# Item.net
KiCad netlist of a schematic drawn in Altium Designer
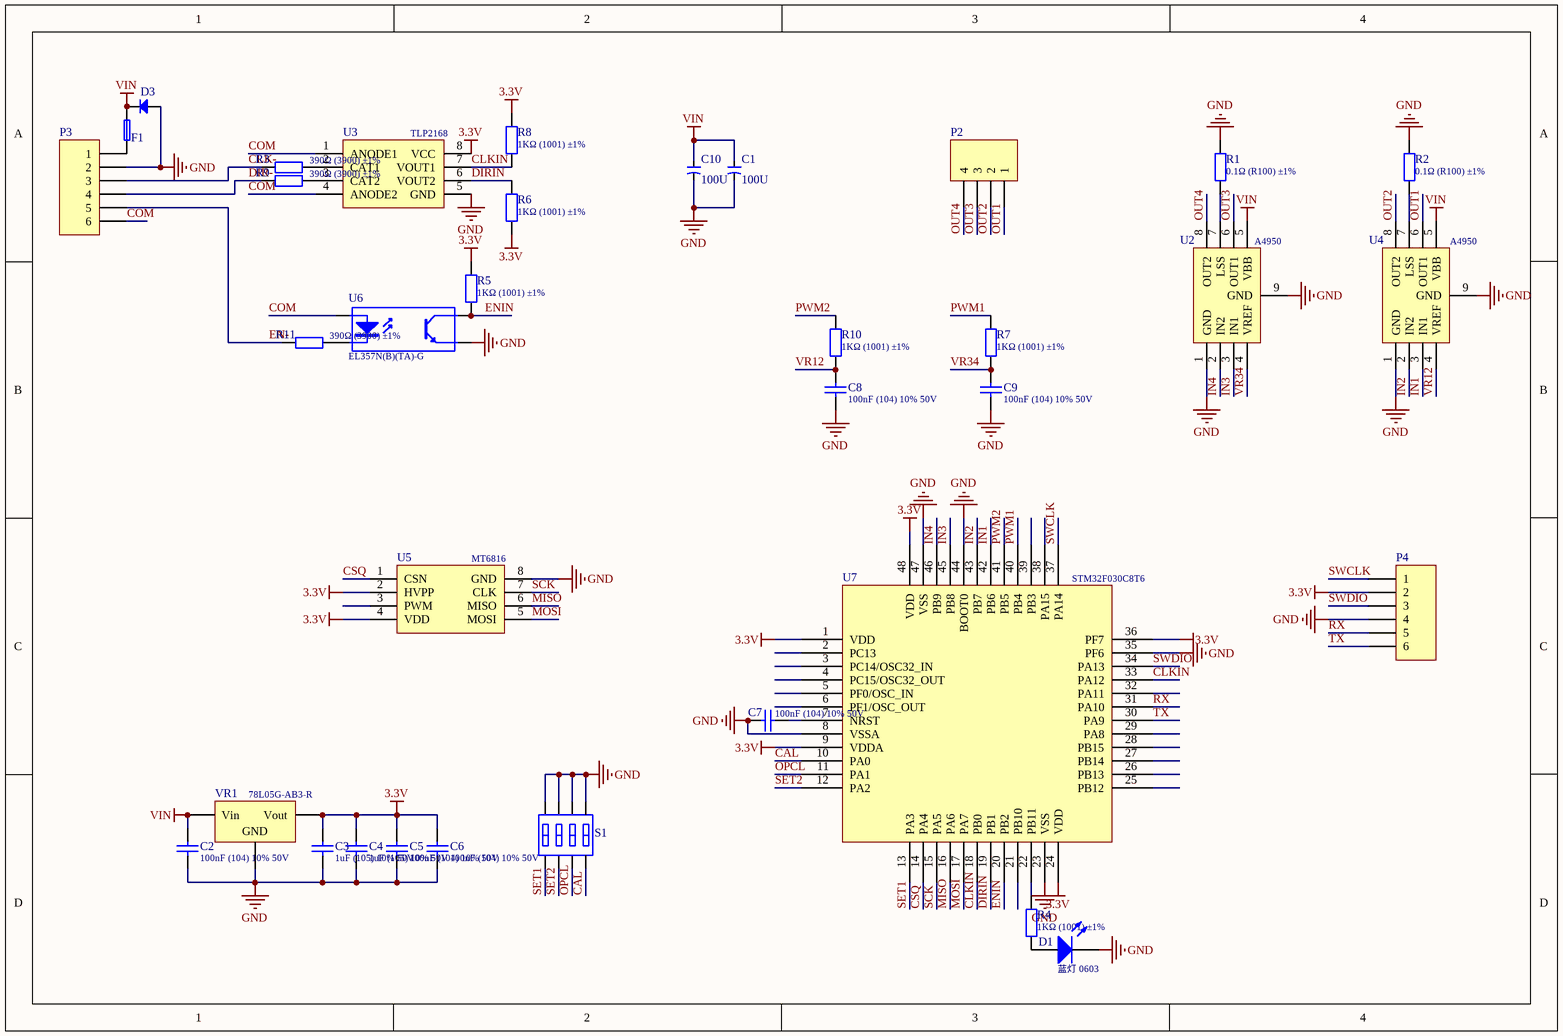
[diagram p0: Item.SchDoc]

(export (version "E")
  (design (tool "Eeschema 10.0.6"))
  (components
    (comp (ref "C1")
      (value "100U")
      (footprint "CAP6377")
      (description "Polarized Capacitor (Axial)")
      (fields (field (name "Comment") "CAP POL") (field (name "PUBLISHER") "Altium Limited"))
      (libsource (lib "MySchib") (part "CAP POL"))
    )
    (comp (ref "C2")
      (value "100nF (104) 10% 50V")
      (footprint "0603_C")
      (description "贴片电容")
      (libsource (lib "Miscellaneous Devices LC") (part "0603 100nF (104) 10% 50V"))
    )
    (comp (ref "C3")
      (value "1uF (105) 10% 50V")
      (footprint "0603_C")
      (description "贴片电容")
      (libsource (lib "Miscellaneous Devices LC") (part "0603 1uF (105) 10% 50V"))
    )
    (comp (ref "C4")
      (value "1uF (105) 10% 50V")
      (footprint "0603_C")
      (description "贴片电容")
      (libsource (lib "Miscellaneous Devices LC") (part "0603 1uF (105) 10% 50V"))
    )
    (comp (ref "C5")
      (value "100nF (104) 10% 50V")
      (footprint "0603_C")
      (description "贴片电容")
      (libsource (lib "Miscellaneous Devices LC") (part "0603 100nF (104) 10% 50V"))
    )
    (comp (ref "C6")
      (value "100nF (104) 10% 50V")
      (footprint "0603_C")
      (description "贴片电容")
      (libsource (lib "Miscellaneous Devices LC") (part "0603 100nF (104) 10% 50V"))
    )
    (comp (ref "C7")
      (value "100nF (104) 10% 50V")
      (footprint "0603_C")
      (description "贴片电容")
      (libsource (lib "Miscellaneous Devices LC") (part "0603 100nF (104) 10% 50V"))
    )
    (comp (ref "C8")
      (value "100nF (104) 10% 50V")
      (footprint "0603_C")
      (description "贴片电容")
      (libsource (lib "Miscellaneous Devices LC") (part "0603 100nF (104) 10% 50V"))
    )
    (comp (ref "C9")
      (value "100nF (104) 10% 50V")
      (footprint "0603_C")
      (description "贴片电容")
      (libsource (lib "Miscellaneous Devices LC") (part "0603 100nF (104) 10% 50V"))
    )
    (comp (ref "C10")
      (value "100U")
      (footprint "CAP6377")
      (description "Polarized Capacitor (Axial)")
      (fields (field (name "Comment") "CAP POL") (field (name "PUBLISHER") "Altium Limited"))
      (libsource (lib "MySchib") (part "CAP POL"))
    )
    (comp (ref "D1")
      (value "蓝灯 0603")
      (footprint "0603_LED_S1")
      (description "发光二极管")
      (libsource (lib "Miscellaneous Devices LC") (part "0603 蓝灯"))
    )
    (comp (ref "D3")
      (value "DIODE")
      (footprint "SOD-123")
      (description "Diode")
      (fields (field (name "PUBLISHER") "Altium Limited"))
      (libsource (lib "MySchib") (part "DIODE"))
    )
    (comp (ref "F1")
      (value "FUSE")
      (footprint "1206_R")
      (description "Fuse")
      (fields (field (name "PUBLISHER") "Altium Limited"))
      (libsource (lib "MySchib") (part "FUSE"))
    )
    (comp (ref "P2")
      (value "HEADER4")
      (footprint "XH-4")
      (description "Header, 4-Pin")
      (fields (field (name "PUBLISHER") "Altium Limited"))
      (libsource (lib "MySchib") (part "HEADER4"))
    )
    (comp (ref "P3")
      (value "HEADER6")
      (footprint "XH-6-S")
      (description "Header, 6-Pin")
      (fields (field (name "PUBLISHER") "Altium Limited"))
      (libsource (lib "") (part "HEADER6_1"))
    )
    (comp (ref "P4")
      (value "HEADER6")
      (footprint "6P-1.27MM")
      (description "Header, 6-Pin")
      (fields (field (name "PUBLISHER") "Altium Limited"))
      (libsource (lib "MySchib") (part "HEADER6"))
    )
    (comp (ref "R1")
      (value "0.1Ω (R100) ±1%")
      (footprint "1206_R")
      (description "贴片电阻")
      (libsource (lib "Miscellaneous Devices LC") (part "1206 0.1Ω (R100) 1%"))
    )
    (comp (ref "R2")
      (value "0.1Ω (R100) ±1%")
      (footprint "1206_R")
      (description "贴片电阻")
      (libsource (lib "Miscellaneous Devices LC") (part "1206 0.1Ω (R100) 1%"))
    )
    (comp (ref "R3")
      (value "390Ω (3900) ±1%")
      (footprint "0603_R")
      (description "贴片电阻")
      (libsource (lib "Miscellaneous Devices LC") (part "0603 390Ω (3900) 1%"))
    )
    (comp (ref "R4")
      (value "1KΩ (1001) ±1%")
      (footprint "0603_R")
      (description "贴片电阻")
      (libsource (lib "Miscellaneous Devices LC") (part "0603 1KΩ (1001) 1%"))
    )
    (comp (ref "R5")
      (value "1KΩ (1001) ±1%")
      (footprint "0603_R")
      (description "贴片电阻")
      (libsource (lib "Miscellaneous Devices LC") (part "0603 1KΩ (1001) 1%"))
    )
    (comp (ref "R6")
      (value "1KΩ (1001) ±1%")
      (footprint "0603_R")
      (description "贴片电阻")
      (libsource (lib "Miscellaneous Devices LC") (part "0603 1KΩ (1001) 1%"))
    )
    (comp (ref "R7")
      (value "1KΩ (1001) ±1%")
      (footprint "0603_R")
      (description "贴片电阻")
      (libsource (lib "Miscellaneous Devices LC") (part "0603 1KΩ (1001) 1%"))
    )
    (comp (ref "R8")
      (value "1KΩ (1001) ±1%")
      (footprint "0603_R")
      (description "贴片电阻")
      (libsource (lib "Miscellaneous Devices LC") (part "0603 1KΩ (1001) 1%"))
    )
    (comp (ref "R9")
      (value "390Ω (3900) ±1%")
      (footprint "0603_R")
      (description "贴片电阻")
      (libsource (lib "Miscellaneous Devices LC") (part "0603 390Ω (3900) 1%"))
    )
    (comp (ref "R10")
      (value "1KΩ (1001) ±1%")
      (footprint "0603_R")
      (description "贴片电阻")
      (libsource (lib "Miscellaneous Devices LC") (part "0603 1KΩ (1001) 1%"))
    )
    (comp (ref "R11")
      (value "390Ω (3900) ±1%")
      (footprint "0603_R")
      (description "贴片电阻")
      (libsource (lib "Miscellaneous Devices LC") (part "0603 390Ω (3900) 1%"))
    )
    (comp (ref "S1")
      (value "SWDIP-4")
      (footprint "SWSUR-4")
      (description "DIP Switch, 4Position, SPST")
      (fields (field (name "PUBLISHER") "Altium Limited"))
      (libsource (lib "MySchib") (part "SWDIP-4"))
    )
    (comp (ref "U2")
      (value "A4950")
      (footprint "SOIC-8_A4950")
      (description "Dual Full-Bridge  DMOS PWM Motor Driver")
      (libsource (lib "MySchib") (part "A4950"))
    )
    (comp (ref "U3")
      (value "TLP2168")
      (footprint "SO-8_3.9mm")
      (description "HIGH SPEED 10MBit/s LOGIC GATE  PHOTOCOUPLER")
      (libsource (lib "MySchib") (part "TLP2168"))
    )
    (comp (ref "U4")
      (value "A4950")
      (footprint "SOIC-8_A4950")
      (description "Dual Full-Bridge  DMOS PWM Motor Driver")
      (libsource (lib "MySchib") (part "A4950"))
    )
    (comp (ref "U5")
      (value "MT6816")
      (footprint "PG-DSO-8S")
      (description "GMR-Based Angle Sensor")
      (libsource (lib "MySchib") (part "MT6816"))
    )
    (comp (ref "U6")
      (value "EL357N(B)(TA)-G")
      (footprint "SOP-4_P2.54")
      (description "贴片光耦")
      (libsource (lib "Miscellaneous Devices LC") (part "EL357N(B)(TA)-G_[C6649]"))
    )
    (comp (ref "U7")
      (value "STM32F030C8T6")
      (footprint "LQFP-48_7x7x05P")
      (description "ARM")
      (libsource (lib "Miscellaneous Devices LC") (part "STM32F030C8T6"))
    )
    (comp (ref "VR1")
      (value "78L05G-AB3-R")
      (footprint "SOT-89(SOT-89-3)")
      (description "低压差线性稳压(LDO)")
      (libsource (lib "Miscellaneous Devices LC") (part "SOT-89 78L05G-AB3-R"))
    )
  )
  (nets
    (net (code "1") (name "/CAL") (class "Default")
      (node (ref "S1") (pin "7") (pinfunction "A4_7") (pintype "passive"))
      (node (ref "U7") (pin "10") (pinfunction "PA0_10") (pintype "passive"))
    )
    (net (code "2") (name "/CLK-") (class "Default")
      (node (ref "P3") (pin "3") (pinfunction "3_3") (pintype "passive"))
      (node (ref "R3") (pin "1") (pinfunction "1_1") (pintype "passive"))
    )
    (net (code "3") (name "/CLKIN") (class "Default")
      (node (ref "R8") (pin "1") (pinfunction "1_1") (pintype "passive"))
      (node (ref "U3") (pin "7") (pinfunction "VOUT1_7") (pintype "passive"))
      (node (ref "U7") (pin "18") (pinfunction "PB0_18") (pintype "passive"))
      (node (ref "U7") (pin "33") (pinfunction "PA12_33") (pintype "passive"))
    )
    (net (code "4") (name "/COM") (class "Default")
      (node (ref "P3") (pin "6") (pinfunction "6_6") (pintype "passive"))
      (node (ref "U3") (pin "1") (pinfunction "ANODE1_1") (pintype "passive"))
      (node (ref "U3") (pin "4") (pinfunction "ANODE2_4") (pintype "passive"))
      (node (ref "U6") (pin "1") (pinfunction "A_1") (pintype "passive"))
    )
    (net (code "5") (name "/CSQ") (class "Default")
      (node (ref "U5") (pin "1") (pinfunction "CSN_1") (pintype "passive"))
      (node (ref "U7") (pin "14") (pinfunction "PA4_14") (pintype "passive"))
    )
    (net (code "6") (name "/DIR-") (class "Default")
      (node (ref "P3") (pin "4") (pinfunction "4_4") (pintype "passive"))
      (node (ref "R9") (pin "1") (pinfunction "1_1") (pintype "passive"))
    )
    (net (code "7") (name "/DIRIN") (class "Default")
      (node (ref "R6") (pin "2") (pinfunction "2_2") (pintype "passive"))
      (node (ref "U3") (pin "6") (pinfunction "VOUT2_6") (pintype "passive"))
      (node (ref "U7") (pin "19") (pinfunction "PB1_19") (pintype "passive"))
    )
    (net (code "8") (name "/EN-") (class "Default")
      (node (ref "P3") (pin "5") (pinfunction "5_5") (pintype "passive"))
      (node (ref "R11") (pin "1") (pinfunction "1_1") (pintype "passive"))
    )
    (net (code "9") (name "/ENIN") (class "Default")
      (node (ref "R5") (pin "1") (pinfunction "1_1") (pintype "passive"))
      (node (ref "U6") (pin "4") (pinfunction "C_4") (pintype "passive"))
      (node (ref "U7") (pin "20") (pinfunction "PB2_20") (pintype "passive"))
    )
    (net (code "10") (name "/IN1") (class "Default")
      (node (ref "U4") (pin "3") (pinfunction "IN1_3") (pintype "passive"))
      (node (ref "U7") (pin "42") (pinfunction "PB6_42") (pintype "passive"))
    )
    (net (code "11") (name "/IN2") (class "Default")
      (node (ref "U4") (pin "2") (pinfunction "IN2_2") (pintype "passive"))
      (node (ref "U7") (pin "43") (pinfunction "PB7_43") (pintype "passive"))
    )
    (net (code "12") (name "/IN3") (class "Default")
      (node (ref "U2") (pin "3") (pinfunction "IN1_3") (pintype "passive"))
      (node (ref "U7") (pin "45") (pinfunction "PB8_45") (pintype "passive"))
    )
    (net (code "13") (name "/IN4") (class "Default")
      (node (ref "U2") (pin "2") (pinfunction "IN2_2") (pintype "passive"))
      (node (ref "U7") (pin "46") (pinfunction "PB9_46") (pintype "passive"))
    )
    (net (code "14") (name "/MISO") (class "Default")
      (node (ref "U5") (pin "6") (pinfunction "MISO_6") (pintype "passive"))
      (node (ref "U7") (pin "16") (pinfunction "PA6_16") (pintype "passive"))
    )
    (net (code "15") (name "/MOSI") (class "Default")
      (node (ref "U5") (pin "5") (pinfunction "MOSI_5") (pintype "passive"))
      (node (ref "U7") (pin "17") (pinfunction "PA7_17") (pintype "passive"))
    )
    (net (code "16") (name "/OPCL") (class "Default")
      (node (ref "S1") (pin "5") (pinfunction "A3_5") (pintype "passive"))
      (node (ref "U7") (pin "11") (pinfunction "PA1_11") (pintype "passive"))
    )
    (net (code "17") (name "/OUT1") (class "Default")
      (node (ref "P2") (pin "1") (pinfunction "1_1") (pintype "passive"))
      (node (ref "U4") (pin "6") (pinfunction "OUT1_6") (pintype "passive"))
    )
    (net (code "18") (name "/OUT2") (class "Default")
      (node (ref "P2") (pin "2") (pinfunction "2_2") (pintype "passive"))
      (node (ref "U4") (pin "8") (pinfunction "OUT2_8") (pintype "passive"))
    )
    (net (code "19") (name "/OUT3") (class "Default")
      (node (ref "P2") (pin "3") (pinfunction "3_3") (pintype "passive"))
      (node (ref "U2") (pin "6") (pinfunction "OUT1_6") (pintype "passive"))
    )
    (net (code "20") (name "/OUT4") (class "Default")
      (node (ref "P2") (pin "4") (pinfunction "4_4") (pintype "passive"))
      (node (ref "U2") (pin "8") (pinfunction "OUT2_8") (pintype "passive"))
    )
    (net (code "21") (name "/PWM1") (class "Default")
      (node (ref "R7") (pin "2") (pinfunction "2_2") (pintype "passive"))
      (node (ref "U7") (pin "40") (pinfunction "PB4_40") (pintype "passive"))
    )
    (net (code "22") (name "/PWM2") (class "Default")
      (node (ref "R10") (pin "2") (pinfunction "2_2") (pintype "passive"))
      (node (ref "U7") (pin "41") (pinfunction "PB5_41") (pintype "passive"))
    )
    (net (code "23") (name "/RX") (class "Default")
      (node (ref "P4") (pin "5") (pinfunction "5_5") (pintype "passive"))
      (node (ref "U7") (pin "31") (pinfunction "PA10_31") (pintype "passive"))
    )
    (net (code "24") (name "/SCK") (class "Default")
      (node (ref "U5") (pin "7") (pinfunction "CLK_7") (pintype "passive"))
      (node (ref "U7") (pin "15") (pinfunction "PA5_15") (pintype "passive"))
    )
    (net (code "25") (name "/SET1") (class "Default")
      (node (ref "S1") (pin "1") (pinfunction "A1_1") (pintype "passive"))
      (node (ref "U7") (pin "13") (pinfunction "PA3_13") (pintype "passive"))
    )
    (net (code "26") (name "/SET2") (class "Default")
      (node (ref "S1") (pin "3") (pinfunction "A2_3") (pintype "passive"))
      (node (ref "U7") (pin "12") (pinfunction "PA2_12") (pintype "passive"))
    )
    (net (code "27") (name "/SWCLK") (class "Default")
      (node (ref "P4") (pin "1") (pinfunction "1_1") (pintype "passive"))
      (node (ref "U7") (pin "37") (pinfunction "PA14_37") (pintype "passive"))
    )
    (net (code "28") (name "/SWDIO") (class "Default")
      (node (ref "P4") (pin "3") (pinfunction "3_3") (pintype "passive"))
      (node (ref "U7") (pin "34") (pinfunction "PA13_34") (pintype "passive"))
    )
    (net (code "29") (name "/TX") (class "Default")
      (node (ref "P4") (pin "6") (pinfunction "6_6") (pintype "passive"))
      (node (ref "U7") (pin "30") (pinfunction "PA9_30") (pintype "passive"))
    )
    (net (code "30") (name "/VR12") (class "Default")
      (node (ref "C8") (pin "2") (pinfunction "2_2") (pintype "passive"))
      (node (ref "R10") (pin "1") (pinfunction "1_1") (pintype "passive"))
      (node (ref "U4") (pin "4") (pinfunction "VREF_4") (pintype "passive"))
    )
    (net (code "31") (name "/VR34") (class "Default")
      (node (ref "C9") (pin "2") (pinfunction "2_2") (pintype "passive"))
      (node (ref "R7") (pin "1") (pinfunction "1_1") (pintype "passive"))
      (node (ref "U2") (pin "4") (pinfunction "VREF_4") (pintype "passive"))
    )
    (net (code "32") (name "3.3V") (class "Default")
      (node (ref "C3") (pin "2") (pinfunction "2_2") (pintype "passive"))
      (node (ref "C4") (pin "2") (pinfunction "2_2") (pintype "passive"))
      (node (ref "C5") (pin "1") (pinfunction "1_1") (pintype "passive"))
      (node (ref "C6") (pin "1") (pinfunction "1_1") (pintype "passive"))
      (node (ref "P4") (pin "2") (pinfunction "2_2") (pintype "passive"))
      (node (ref "R5") (pin "2") (pinfunction "2_2") (pintype "passive"))
      (node (ref "R6") (pin "1") (pinfunction "1_1") (pintype "passive"))
      (node (ref "R8") (pin "2") (pinfunction "2_2") (pintype "passive"))
      (node (ref "U3") (pin "8") (pinfunction "VCC_8") (pintype "passive"))
      (node (ref "U5") (pin "2") (pinfunction "HVPP_2") (pintype "passive"))
      (node (ref "U5") (pin "4") (pinfunction "VDD_4") (pintype "passive"))
      (node (ref "U7") (pin "1") (pinfunction "VDD_1") (pintype "passive"))
      (node (ref "U7") (pin "24") (pinfunction "VDD_24") (pintype "passive"))
      (node (ref "U7") (pin "36") (pinfunction "PF7_36") (pintype "passive"))
      (node (ref "U7") (pin "48") (pinfunction "VDD_48") (pintype "passive"))
      (node (ref "U7") (pin "9") (pinfunction "VDDA_9") (pintype "passive"))
      (node (ref "VR1") (pin "1") (pinfunction "Vout_1") (pintype "passive"))
    )
    (net (code "33") (name "GND") (class "Default")
      (node (ref "C1") (pin "2") (pinfunction "2_2") (pintype "passive"))
      (node (ref "C10") (pin "2") (pinfunction "2_2") (pintype "passive"))
      (node (ref "C2") (pin "2") (pinfunction "2_2") (pintype "passive"))
      (node (ref "C3") (pin "1") (pinfunction "1_1") (pintype "passive"))
      (node (ref "C4") (pin "1") (pinfunction "1_1") (pintype "passive"))
      (node (ref "C5") (pin "2") (pinfunction "2_2") (pintype "passive"))
      (node (ref "C6") (pin "2") (pinfunction "2_2") (pintype "passive"))
      (node (ref "C7") (pin "2") (pinfunction "2_2") (pintype "passive"))
      (node (ref "C8") (pin "1") (pinfunction "1_1") (pintype "passive"))
      (node (ref "C9") (pin "1") (pinfunction "1_1") (pintype "passive"))
      (node (ref "D1") (pin "K") (pinfunction "K_K") (pintype "passive"))
      (node (ref "D3") (pin "1") (pinfunction "A_1") (pintype "passive"))
      (node (ref "P3") (pin "2") (pinfunction "2_2") (pintype "passive"))
      (node (ref "P4") (pin "4") (pinfunction "4_4") (pintype "passive"))
      (node (ref "R1") (pin "1") (pinfunction "1_1") (pintype "passive"))
      (node (ref "R2") (pin "1") (pinfunction "1_1") (pintype "passive"))
      (node (ref "S1") (pin "2") (pinfunction "B1_2") (pintype "passive"))
      (node (ref "S1") (pin "4") (pinfunction "B2_4") (pintype "passive"))
      (node (ref "S1") (pin "6") (pinfunction "B3_6") (pintype "passive"))
      (node (ref "S1") (pin "8") (pinfunction "B4_8") (pintype "passive"))
      (node (ref "U2") (pin "1") (pinfunction "GND_1") (pintype "passive"))
      (node (ref "U2") (pin "9") (pinfunction "GND_9") (pintype "passive"))
      (node (ref "U3") (pin "5") (pinfunction "GND_5") (pintype "passive"))
      (node (ref "U4") (pin "1") (pinfunction "GND_1") (pintype "passive"))
      (node (ref "U4") (pin "9") (pinfunction "GND_9") (pintype "passive"))
      (node (ref "U5") (pin "8") (pinfunction "GND_8") (pintype "passive"))
      (node (ref "U6") (pin "3") (pinfunction "E_3") (pintype "passive"))
      (node (ref "U7") (pin "23") (pinfunction "VSS_23") (pintype "passive"))
      (node (ref "U7") (pin "35") (pinfunction "PF6_35") (pintype "passive"))
      (node (ref "U7") (pin "44") (pinfunction "BOOT0_44") (pintype "passive"))
      (node (ref "U7") (pin "47") (pinfunction "VSS_47") (pintype "passive"))
      (node (ref "U7") (pin "8") (pinfunction "VSSA_8") (pintype "passive"))
      (node (ref "VR1") (pin "2") (pinfunction "GND_2") (pintype "passive"))
    )
    (net (code "34") (name "Net-(D1-PadA)") (class "Default")
      (node (ref "D1") (pin "A") (pinfunction "A_A") (pintype "passive"))
      (node (ref "R4") (pin "1") (pinfunction "1_1") (pintype "passive"))
    )
    (net (code "35") (name "Net-(F1-Pad1)") (class "Default")
      (node (ref "F1") (pin "1") (pinfunction "1_1") (pintype "passive"))
      (node (ref "P3") (pin "1") (pinfunction "1_1") (pintype "passive"))
    )
    (net (code "36") (name "Net-(U2-LSS)") (class "Default")
      (node (ref "R1") (pin "2") (pinfunction "2_2") (pintype "passive"))
      (node (ref "U2") (pin "7") (pinfunction "LSS_7") (pintype "passive"))
    )
    (net (code "37") (name "Net-(U3-CAT1)") (class "Default")
      (node (ref "R3") (pin "2") (pinfunction "2_2") (pintype "passive"))
      (node (ref "U3") (pin "2") (pinfunction "CAT1_2") (pintype "passive"))
    )
    (net (code "38") (name "Net-(U3-CAT2)") (class "Default")
      (node (ref "R9") (pin "2") (pinfunction "2_2") (pintype "passive"))
      (node (ref "U3") (pin "3") (pinfunction "CAT2_3") (pintype "passive"))
    )
    (net (code "39") (name "Net-(U4-LSS)") (class "Default")
      (node (ref "R2") (pin "2") (pinfunction "2_2") (pintype "passive"))
      (node (ref "U4") (pin "7") (pinfunction "LSS_7") (pintype "passive"))
    )
    (net (code "40") (name "Net-(U6-K)") (class "Default")
      (node (ref "R11") (pin "2") (pinfunction "2_2") (pintype "passive"))
      (node (ref "U6") (pin "2") (pinfunction "K_2") (pintype "passive"))
    )
    (net (code "41") (name "Net-(U7-NRST)") (class "Default")
      (node (ref "C7") (pin "1") (pinfunction "1_1") (pintype "passive"))
      (node (ref "U7") (pin "7") (pinfunction "NRST_7") (pintype "passive"))
    )
    (net (code "42") (name "Net-(U7-PB11)") (class "Default")
      (node (ref "R4") (pin "2") (pinfunction "2_2") (pintype "passive"))
      (node (ref "U7") (pin "22") (pinfunction "PB11_22") (pintype "passive"))
    )
    (net (code "43") (name "VIN") (class "Default")
      (node (ref "C1") (pin "1") (pinfunction "1_1") (pintype "passive"))
      (node (ref "C10") (pin "1") (pinfunction "1_1") (pintype "passive"))
      (node (ref "C2") (pin "1") (pinfunction "1_1") (pintype "passive"))
      (node (ref "D3") (pin "2") (pinfunction "K_2") (pintype "passive"))
      (node (ref "F1") (pin "2") (pinfunction "2_2") (pintype "passive"))
      (node (ref "U2") (pin "5") (pinfunction "VBB_5") (pintype "passive"))
      (node (ref "U4") (pin "5") (pinfunction "VBB_5") (pintype "passive"))
      (node (ref "VR1") (pin "3") (pinfunction "Vin_3") (pintype "passive"))
    )
    (net (code "44") (name "unconnected-(U5-PWM-Pad3)") (class "Default")
      (node (ref "U5") (pin "3") (pinfunction "PWM_3") (pintype "passive"))
    )
    (net (code "45") (name "unconnected-(U7-PA8-Pad29)") (class "Default")
      (node (ref "U7") (pin "29") (pinfunction "PA8_29") (pintype "passive"))
    )
    (net (code "46") (name "unconnected-(U7-PA11-Pad32)") (class "Default")
      (node (ref "U7") (pin "32") (pinfunction "PA11_32") (pintype "passive"))
    )
    (net (code "47") (name "unconnected-(U7-PA15-Pad38)") (class "Default")
      (node (ref "U7") (pin "38") (pinfunction "PA15_38") (pintype "passive"))
    )
    (net (code "48") (name "unconnected-(U7-PB3-Pad39)") (class "Default")
      (node (ref "U7") (pin "39") (pinfunction "PB3_39") (pintype "passive"))
    )
    (net (code "49") (name "unconnected-(U7-PB10-Pad21)") (class "Default")
      (node (ref "U7") (pin "21") (pinfunction "PB10_21") (pintype "passive"))
    )
    (net (code "50") (name "unconnected-(U7-PB12-Pad25)") (class "Default")
      (node (ref "U7") (pin "25") (pinfunction "PB12_25") (pintype "passive"))
    )
    (net (code "51") (name "unconnected-(U7-PB13-Pad26)") (class "Default")
      (node (ref "U7") (pin "26") (pinfunction "PB13_26") (pintype "passive"))
    )
    (net (code "52") (name "unconnected-(U7-PB14-Pad27)") (class "Default")
      (node (ref "U7") (pin "27") (pinfunction "PB14_27") (pintype "passive"))
    )
    (net (code "53") (name "unconnected-(U7-PB15-Pad28)") (class "Default")
      (node (ref "U7") (pin "28") (pinfunction "PB15_28") (pintype "passive"))
    )
    (net (code "54") (name "unconnected-(U7-PC13-Pad2)") (class "Default")
      (node (ref "U7") (pin "2") (pinfunction "PC13_2") (pintype "passive"))
    )
    (net (code "55") (name "unconnected-(U7-PC14{slash}OSC32_IN-Pad3)") (class "Default")
      (node (ref "U7") (pin "3") (pinfunction "PC14/OSC32_IN_3") (pintype "passive"))
    )
    (net (code "56") (name "unconnected-(U7-PC15{slash}OSC32_OUT-Pad4)") (class "Default")
      (node (ref "U7") (pin "4") (pinfunction "PC15/OSC32_OUT_4") (pintype "passive"))
    )
    (net (code "57") (name "unconnected-(U7-PF0{slash}OSC_IN-Pad5)") (class "Default")
      (node (ref "U7") (pin "5") (pinfunction "PF0/OSC_IN_5") (pintype "passive"))
    )
    (net (code "58") (name "unconnected-(U7-PF1{slash}OSC_OUT-Pad6)") (class "Default")
      (node (ref "U7") (pin "6") (pinfunction "PF1/OSC_OUT_6") (pintype "passive"))
    )
  )
)
